# ladowarka.net
KiCad netlist of a schematic drawn in Altium Designer
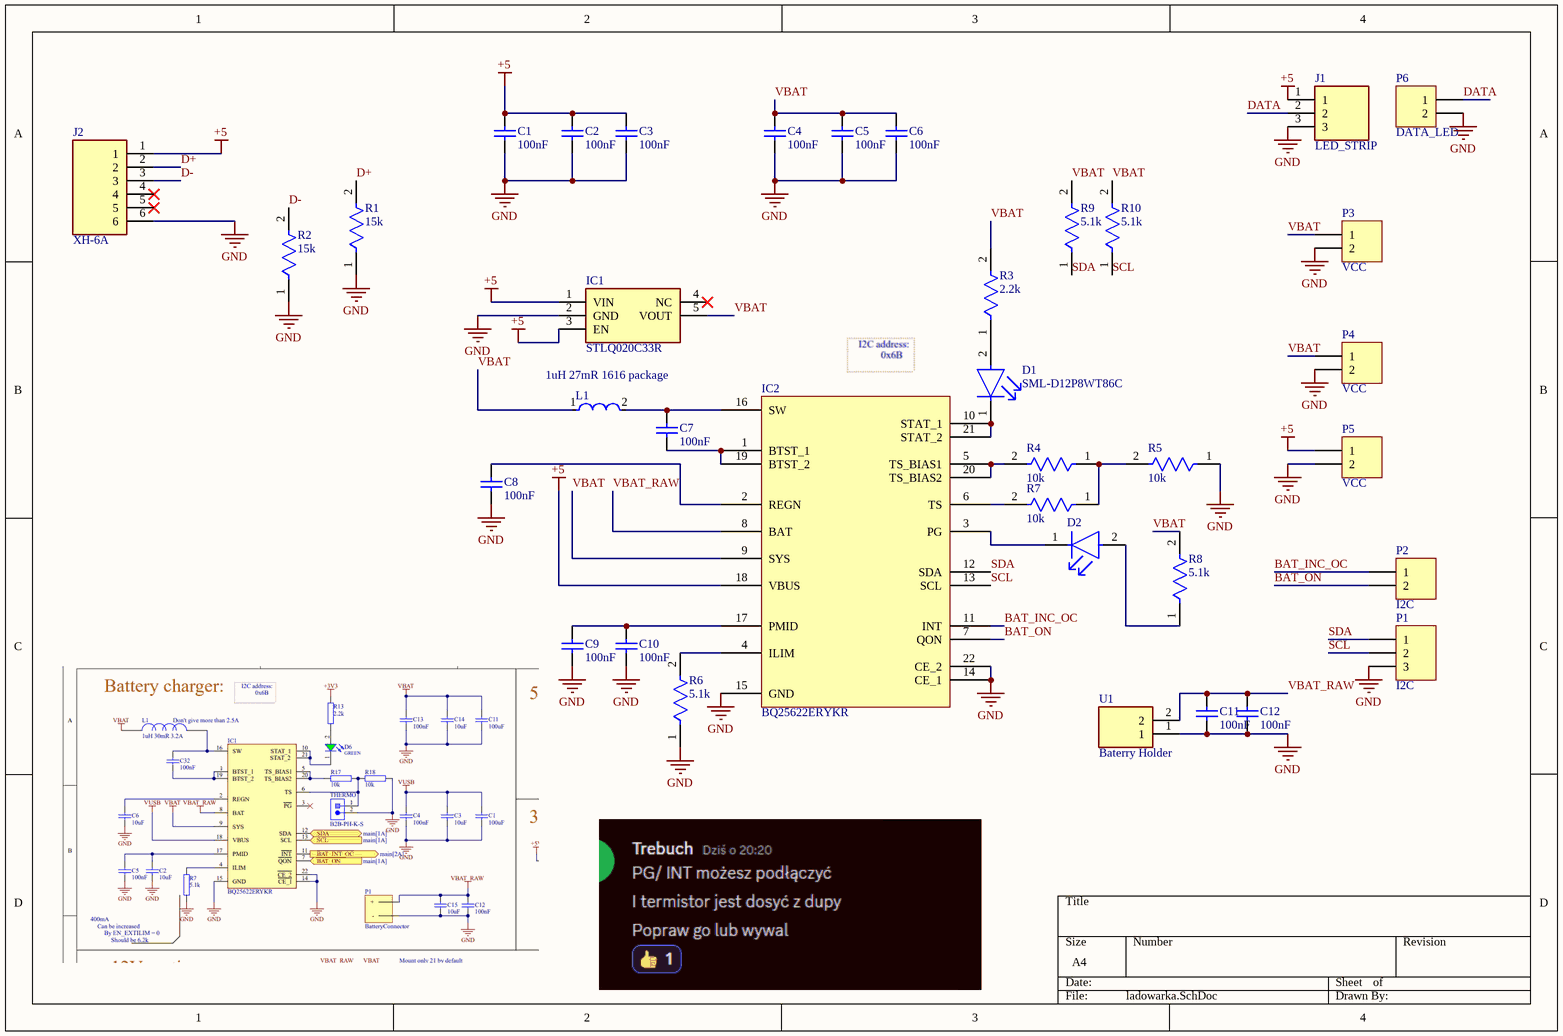
[diagram p0: ladowarka.SchDoc]

(export (version "E")
  (design (tool "Eeschema 10.0.6"))
  (components
    (comp (ref "C1")
      (value "100nF")
      (footprint "1608[0603]")
      (description "Capacitor (Semiconductor SIM Model)")
      (fields (field (name "PUBLISHER") "Altium Limited"))
      (libsource (lib "Miscellaneous Devices") (part "Cap Semi"))
    )
    (comp (ref "C2")
      (value "100nF")
      (footprint "1608[0603]")
      (description "Capacitor (Semiconductor SIM Model)")
      (fields (field (name "PUBLISHER") "Altium Limited"))
      (libsource (lib "Miscellaneous Devices") (part "Cap Semi"))
    )
    (comp (ref "C3")
      (value "100nF")
      (footprint "1608[0603]")
      (description "Capacitor (Semiconductor SIM Model)")
      (fields (field (name "PUBLISHER") "Altium Limited"))
      (libsource (lib "Miscellaneous Devices") (part "Cap Semi"))
    )
    (comp (ref "C4")
      (value "100nF")
      (footprint "1608[0603]")
      (description "Capacitor (Semiconductor SIM Model)")
      (fields (field (name "PUBLISHER") "Altium Limited"))
      (libsource (lib "Miscellaneous Devices") (part "Cap Semi"))
    )
    (comp (ref "C5")
      (value "100nF")
      (footprint "1608[0603]")
      (description "Capacitor (Semiconductor SIM Model)")
      (fields (field (name "PUBLISHER") "Altium Limited"))
      (libsource (lib "Miscellaneous Devices") (part "Cap Semi"))
    )
    (comp (ref "C6")
      (value "100nF")
      (footprint "1608[0603]")
      (description "Capacitor (Semiconductor SIM Model)")
      (fields (field (name "PUBLISHER") "Altium Limited"))
      (libsource (lib "Miscellaneous Devices") (part "Cap Semi"))
    )
    (comp (ref "C7")
      (value "100nF")
      (footprint "1608[0603]")
      (description "Capacitor (Semiconductor SIM Model)")
      (fields (field (name "PUBLISHER") "Altium Limited"))
      (libsource (lib "Miscellaneous Devices") (part "Cap Semi"))
    )
    (comp (ref "C8")
      (value "100nF")
      (footprint "1608[0603]")
      (description "Capacitor (Semiconductor SIM Model)")
      (fields (field (name "PUBLISHER") "Altium Limited"))
      (libsource (lib "Miscellaneous Devices") (part "Cap Semi"))
    )
    (comp (ref "C9")
      (value "100nF")
      (footprint "1608[0603]")
      (description "Capacitor (Semiconductor SIM Model)")
      (fields (field (name "PUBLISHER") "Altium Limited"))
      (libsource (lib "Miscellaneous Devices") (part "Cap Semi"))
    )
    (comp (ref "C10")
      (value "100nF")
      (footprint "1608[0603]")
      (description "Capacitor (Semiconductor SIM Model)")
      (fields (field (name "PUBLISHER") "Altium Limited"))
      (libsource (lib "Miscellaneous Devices") (part "Cap Semi"))
    )
    (comp (ref "C11")
      (value "100nF")
      (footprint "1608[0603]")
      (description "Capacitor (Semiconductor SIM Model)")
      (fields (field (name "PUBLISHER") "Altium Limited"))
      (libsource (lib "Miscellaneous Devices") (part "Cap Semi"))
    )
    (comp (ref "C12")
      (value "100nF")
      (footprint "1608[0603]")
      (description "Capacitor (Semiconductor SIM Model)")
      (fields (field (name "PUBLISHER") "Altium Limited"))
      (libsource (lib "Miscellaneous Devices") (part "Cap Semi"))
    )
    (comp (ref "D1")
      (value "SML-D12P8WT86C")
      (footprint "FP-SML-D12-MFG")
      (description "LED GREEN 1608 SMD")
      (fields
        (field (name "OCTOPART") "https://octopart.com/sml-d12p8wt86c-rohm-77740213")
        (field (name "MANUFACTURER") "Rohm")
      )
      (libsource (lib "Altium Content Vault") (part "8706943c75ba83719d021d2fdc84c58"))
    )
    (comp (ref "D2")
      (value "SML-D12P8WT86C")
      (footprint "FP-SML-D12-MFG")
      (description "LED GREEN 1608 SMD")
      (fields
        (field (name "OCTOPART") "https://octopart.com/sml-d12p8wt86c-rohm-77740213")
        (field (name "MANUFACTURER") "Rohm")
      )
      (libsource (lib "Altium Content Vault") (part "8706943c75ba83719d021d2fdc84c58"))
    )
    (comp (ref "IC1")
      (value "STLQ020C33R")
      (footprint "SamacSys:SOT65P210X110-5N")
      (description "Integrated Circuit")
      (fields (field (name "MOUSER PART NUMBER") "511-STLQ020C33R"))
      (libsource (lib "*") (part "STLQ020C33R"))
    )
    (comp (ref "IC2")
      (value "BQ25622ERYKR")
      (footprint "SamacSys:BQ25620RYKR")
      (description "Integrated Circuit")
      (fields
        (field (name "MANUFACTURER_PART_NUMBER") "BQ25620RYKR")
        (field (name "MOUSER PART NUMBER") "595-BQ25620RYKR")
      )
      (libsource (lib "SamacSys") (part "BQ25622ERYKR"))
    )
    (comp (ref "J1")
      (value "LED_STRIP")
      (footprint "SamacSys:SHDR3W64P0X250_1X3_990X575X700P")
      (description "Connector")
      (fields (field (name "MANUFACTURER_PART_NUMBER") "B3B-XH-A"))
      (libsource (lib "*") (part "B3B-XH-A"))
    )
    (comp (ref "J2")
      (value "XH-6A")
      (footprint "SamacSys:SHDR6W64P0X250_1X6_1750X580X720P")
      (description "Connector")
      (libsource (lib "*") (part "XH-6A"))
    )
    (comp (ref "L1")
      (value "1uH 27mR 1616 package")
      (footprint "FP-IHLP-1616BZ-FP_1_8545x-MFG")
      (description "Fixed Inductors Commercial Low DCR Series SMT 1uH 4.5A 27mΩ 20%")
      (fields (field (name "TOLERANCE") "20%"))
      (libsource (lib "Altium Content Vault") (part "725321dda6339637d4d059423bc1c3c"))
    )
    (comp (ref "P1")
      (value "I2C")
      (footprint "HDR1X3")
      (description "Header, 3-Pin")
      (fields (field (name "PUBLISHER") "Altium Limited"))
      (libsource (lib "Miscellaneous Connectors") (part "Header 3"))
    )
    (comp (ref "P2")
      (value "I2C")
      (footprint "HDR1X2")
      (description "Header, 2-Pin")
      (fields (field (name "PUBLISHER") "Altium Limited"))
      (libsource (lib "Miscellaneous Connectors") (part "Header 2"))
    )
    (comp (ref "P3")
      (value "VCC")
      (footprint "HDR1X2")
      (description "Header, 2-Pin")
      (fields (field (name "PUBLISHER") "Altium Limited"))
      (libsource (lib "Miscellaneous Connectors") (part "Header 2"))
    )
    (comp (ref "P4")
      (value "VCC")
      (footprint "HDR1X2")
      (description "Header, 2-Pin")
      (fields (field (name "PUBLISHER") "Altium Limited"))
      (libsource (lib "Miscellaneous Connectors") (part "Header 2"))
    )
    (comp (ref "P5")
      (value "VCC")
      (footprint "HDR1X2")
      (description "Header, 2-Pin")
      (fields (field (name "PUBLISHER") "Altium Limited"))
      (libsource (lib "Miscellaneous Connectors") (part "Header 2"))
    )
    (comp (ref "P6")
      (value "DATA_LED")
      (footprint "HDR1X2")
      (description "Header, 2-Pin")
      (fields (field (name "PUBLISHER") "Altium Limited"))
      (libsource (lib "") (part "Header 2_1"))
    )
    (comp (ref "R1")
      (value "15k")
      (footprint "FP-CRCW0603-e3-MFG")
      (description "RES Thick Film, 10kΩ, 1%, 0.1W, 100ppm/°C, 0603")
      (fields (field (name "TOLERANCE") "1%"))
      (libsource (lib "Altium Content Vault") (part "1029c3af85768c4190bb7ad29bc67b5"))
    )
    (comp (ref "R2")
      (value "15k")
      (footprint "FP-CRCW0603-e3-MFG")
      (description "RES Thick Film, 10kΩ, 1%, 0.1W, 100ppm/°C, 0603")
      (fields (field (name "TOLERANCE") "1%"))
      (libsource (lib "Altium Content Vault") (part "1029c3af85768c4190bb7ad29bc67b5"))
    )
    (comp (ref "R3")
      (value "2.2k")
      (footprint "FP-CRCW0603-e3-MFG")
      (description "RES Thick Film, 10kΩ, 1%, 0.1W, 100ppm/°C, 0603")
      (fields (field (name "TOLERANCE") "1%"))
      (libsource (lib "Altium Content Vault") (part "1029c3af85768c4190bb7ad29bc67b5"))
    )
    (comp (ref "R4")
      (value "10k")
      (footprint "FP-CRCW0603-e3-MFG")
      (description "RES Thick Film, 10kΩ, 1%, 0.1W, 100ppm/°C, 0603")
      (fields (field (name "TOLERANCE") "1%"))
      (libsource (lib "Altium Content Vault") (part "1029c3af85768c4190bb7ad29bc67b5"))
    )
    (comp (ref "R5")
      (value "10k")
      (footprint "FP-CRCW0603-e3-MFG")
      (description "RES Thick Film, 10kΩ, 1%, 0.1W, 100ppm/°C, 0603")
      (fields (field (name "TOLERANCE") "1%"))
      (libsource (lib "Altium Content Vault") (part "1029c3af85768c4190bb7ad29bc67b5"))
    )
    (comp (ref "R6")
      (value "5.1k")
      (footprint "FP-CRCW0603-e3-MFG")
      (description "RES Thick Film, 10kΩ, 1%, 0.1W, 100ppm/°C, 0603")
      (fields (field (name "TOLERANCE") "1%"))
      (libsource (lib "Altium Content Vault") (part "1029c3af85768c4190bb7ad29bc67b5"))
    )
    (comp (ref "R7")
      (value "10k")
      (footprint "FP-CRCW0603-e3-MFG")
      (description "RES Thick Film, 10kΩ, 1%, 0.1W, 100ppm/°C, 0603")
      (fields (field (name "TOLERANCE") "1%"))
      (libsource (lib "Altium Content Vault") (part "1029c3af85768c4190bb7ad29bc67b5"))
    )
    (comp (ref "R8")
      (value "5.1k")
      (footprint "FP-CRCW0603-e3-MFG")
      (description "RES Thick Film, 10kΩ, 1%, 0.1W, 100ppm/°C, 0603")
      (fields (field (name "TOLERANCE") "1%"))
      (libsource (lib "Altium Content Vault") (part "1029c3af85768c4190bb7ad29bc67b5"))
    )
    (comp (ref "R9")
      (value "5.1k")
      (footprint "FP-CRCW0603-e3-MFG")
      (description "RES Thick Film, 10kΩ, 1%, 0.1W, 100ppm/°C, 0603")
      (fields (field (name "TOLERANCE") "1%"))
      (libsource (lib "Altium Content Vault") (part "1029c3af85768c4190bb7ad29bc67b5"))
    )
    (comp (ref "R10")
      (value "5.1k")
      (footprint "FP-CRCW0603-e3-MFG")
      (description "RES Thick Film, 10kΩ, 1%, 0.1W, 100ppm/°C, 0603")
      (fields (field (name "TOLERANCE") "1%"))
      (libsource (lib "Altium Content Vault") (part "1029c3af85768c4190bb7ad29bc67b5"))
    )
    (comp (ref "U1")
      (value "Baterry Holder")
      (footprint "SamacSys:1053")
      (description "Undefined or Miscellaneous")
      (fields
        (field (name "MANUFACTURER_PART_NUMBER") "1053")
        (field (name "MOUSER PART NUMBER") "534-1053-BH")
      )
      (libsource (lib "SamacSys") (part "1053"))
    )
  )
  (nets
    (net (code "1") (name "+5") (class "Default")
      (node (ref "C1") (pin "1") (pinfunction "1_1") (pintype "passive"))
      (node (ref "C2") (pin "1") (pinfunction "1_1") (pintype "passive"))
      (node (ref "C3") (pin "1") (pinfunction "1_1") (pintype "passive"))
      (node (ref "IC1") (pin "1") (pinfunction "VIN_1") (pintype "passive"))
      (node (ref "IC1") (pin "3") (pinfunction "EN_3") (pintype "passive"))
      (node (ref "IC2") (pin "18") (pinfunction "VBUS_18") (pintype "passive"))
      (node (ref "J1") (pin "1") (pinfunction "1_1") (pintype "passive"))
      (node (ref "J2") (pin "1") (pinfunction "1_1") (pintype "passive"))
      (node (ref "P5") (pin "1") (pinfunction "1_1") (pintype "passive"))
    )
    (net (code "2") (name "/BAT_INC_OC") (class "Default")
      (node (ref "IC2") (pin "11") (pinfunction "INT_11") (pintype "passive"))
      (node (ref "P2") (pin "1") (pinfunction "1_1") (pintype "passive"))
    )
    (net (code "3") (name "/BAT_ON") (class "Default")
      (node (ref "IC2") (pin "7") (pinfunction "QON_7") (pintype "passive"))
      (node (ref "P2") (pin "2") (pinfunction "2_2") (pintype "passive"))
    )
    (net (code "4") (name "/D+") (class "Default")
      (node (ref "J2") (pin "2") (pinfunction "2_2") (pintype "passive"))
      (node (ref "R1") (pin "2") (pinfunction "2_2") (pintype "passive"))
    )
    (net (code "5") (name "/D-") (class "Default")
      (node (ref "J2") (pin "3") (pinfunction "3_3") (pintype "passive"))
      (node (ref "R2") (pin "2") (pinfunction "2_2") (pintype "passive"))
    )
    (net (code "6") (name "/DATA") (class "Default")
      (node (ref "J1") (pin "2") (pinfunction "2_2") (pintype "passive"))
      (node (ref "P6") (pin "1") (pinfunction "1_1") (pintype "passive"))
    )
    (net (code "7") (name "/SCL") (class "Default")
      (node (ref "IC2") (pin "13") (pinfunction "SCL_13") (pintype "passive"))
      (node (ref "P1") (pin "2") (pinfunction "2_2") (pintype "passive"))
      (node (ref "R10") (pin "1") (pinfunction "1_1") (pintype "passive"))
    )
    (net (code "8") (name "/SDA") (class "Default")
      (node (ref "IC2") (pin "12") (pinfunction "SDA_12") (pintype "passive"))
      (node (ref "P1") (pin "1") (pinfunction "1_1") (pintype "passive"))
      (node (ref "R9") (pin "1") (pinfunction "1_1") (pintype "passive"))
    )
    (net (code "9") (name "/VBAT") (class "Default")
      (node (ref "C4") (pin "1") (pinfunction "1_1") (pintype "passive"))
      (node (ref "C5") (pin "1") (pinfunction "1_1") (pintype "passive"))
      (node (ref "C6") (pin "1") (pinfunction "1_1") (pintype "passive"))
      (node (ref "IC1") (pin "5") (pinfunction "VOUT_5") (pintype "passive"))
      (node (ref "IC2") (pin "9") (pinfunction "SYS_9") (pintype "passive"))
      (node (ref "L1") (pin "1") (pinfunction "1_1") (pintype "passive"))
      (node (ref "P3") (pin "1") (pinfunction "1_1") (pintype "passive"))
      (node (ref "P4") (pin "1") (pinfunction "1_1") (pintype "passive"))
      (node (ref "R10") (pin "2") (pinfunction "2_2") (pintype "passive"))
      (node (ref "R3") (pin "2") (pinfunction "2_2") (pintype "passive"))
      (node (ref "R8") (pin "2") (pinfunction "2_2") (pintype "passive"))
      (node (ref "R9") (pin "2") (pinfunction "2_2") (pintype "passive"))
    )
    (net (code "10") (name "/VBAT_RAW") (class "Default")
      (node (ref "C11") (pin "1") (pinfunction "1_1") (pintype "passive"))
      (node (ref "C12") (pin "1") (pinfunction "1_1") (pintype "passive"))
      (node (ref "IC2") (pin "8") (pinfunction "BAT_8") (pintype "passive"))
      (node (ref "U1") (pin "2") (pinfunction "2_2") (pintype "passive"))
    )
    (net (code "11") (name "GND") (class "Default")
      (node (ref "C1") (pin "2") (pinfunction "2_2") (pintype "passive"))
      (node (ref "C10") (pin "2") (pinfunction "2_2") (pintype "passive"))
      (node (ref "C11") (pin "2") (pinfunction "2_2") (pintype "passive"))
      (node (ref "C12") (pin "2") (pinfunction "2_2") (pintype "passive"))
      (node (ref "C2") (pin "2") (pinfunction "2_2") (pintype "passive"))
      (node (ref "C3") (pin "2") (pinfunction "2_2") (pintype "passive"))
      (node (ref "C4") (pin "2") (pinfunction "2_2") (pintype "passive"))
      (node (ref "C5") (pin "2") (pinfunction "2_2") (pintype "passive"))
      (node (ref "C6") (pin "2") (pinfunction "2_2") (pintype "passive"))
      (node (ref "C8") (pin "2") (pinfunction "2_2") (pintype "passive"))
      (node (ref "C9") (pin "2") (pinfunction "2_2") (pintype "passive"))
      (node (ref "IC1") (pin "2") (pinfunction "GND_2") (pintype "passive"))
      (node (ref "IC2") (pin "14") (pinfunction "CE_1_14") (pintype "passive"))
      (node (ref "IC2") (pin "15") (pinfunction "GND_15") (pintype "passive"))
      (node (ref "IC2") (pin "22") (pinfunction "CE_2_22") (pintype "passive"))
      (node (ref "J1") (pin "3") (pinfunction "3_3") (pintype "passive"))
      (node (ref "J2") (pin "6") (pinfunction "6_6") (pintype "passive"))
      (node (ref "P1") (pin "3") (pinfunction "3_3") (pintype "passive"))
      (node (ref "P3") (pin "2") (pinfunction "2_2") (pintype "passive"))
      (node (ref "P4") (pin "2") (pinfunction "2_2") (pintype "passive"))
      (node (ref "P5") (pin "2") (pinfunction "2_2") (pintype "passive"))
      (node (ref "P6") (pin "2") (pinfunction "2_2") (pintype "passive"))
      (node (ref "R1") (pin "1") (pinfunction "1_1") (pintype "passive"))
      (node (ref "R2") (pin "1") (pinfunction "1_1") (pintype "passive"))
      (node (ref "R5") (pin "1") (pinfunction "1_1") (pintype "passive"))
      (node (ref "R6") (pin "1") (pinfunction "1_1") (pintype "passive"))
      (node (ref "U1") (pin "1") (pinfunction "1_1") (pintype "passive"))
    )
    (net (code "12") (name "Net-(D1-A)") (class "Default")
      (node (ref "D1") (pin "2") (pinfunction "A_2") (pintype "passive"))
      (node (ref "R3") (pin "1") (pinfunction "1_1") (pintype "passive"))
    )
    (net (code "13") (name "Net-(D1-C)") (class "Default")
      (node (ref "D1") (pin "1") (pinfunction "C_1") (pintype "passive"))
      (node (ref "IC2") (pin "10") (pinfunction "STAT_1_10") (pintype "passive"))
      (node (ref "IC2") (pin "21") (pinfunction "STAT_2_21") (pintype "passive"))
    )
    (net (code "14") (name "Net-(D2-A)") (class "Default")
      (node (ref "D2") (pin "2") (pinfunction "A_2") (pintype "passive"))
      (node (ref "R8") (pin "1") (pinfunction "1_1") (pintype "passive"))
    )
    (net (code "15") (name "Net-(D2-C)") (class "Default")
      (node (ref "D2") (pin "1") (pinfunction "C_1") (pintype "passive"))
      (node (ref "IC2") (pin "3") (pinfunction "PG_3") (pintype "passive"))
    )
    (net (code "16") (name "Net-(IC2-BTST_1)") (class "Default")
      (node (ref "C7") (pin "2") (pinfunction "2_2") (pintype "passive"))
      (node (ref "IC2") (pin "1") (pinfunction "BTST_1_1") (pintype "passive"))
      (node (ref "IC2") (pin "19") (pinfunction "BTST_2_19") (pintype "passive"))
    )
    (net (code "17") (name "Net-(IC2-ILIM)") (class "Default")
      (node (ref "IC2") (pin "4") (pinfunction "ILIM_4") (pintype "passive"))
      (node (ref "R6") (pin "2") (pinfunction "2_2") (pintype "passive"))
    )
    (net (code "18") (name "Net-(IC2-PMID)") (class "Default")
      (node (ref "C10") (pin "1") (pinfunction "1_1") (pintype "passive"))
      (node (ref "C9") (pin "1") (pinfunction "1_1") (pintype "passive"))
      (node (ref "IC2") (pin "17") (pinfunction "PMID_17") (pintype "passive"))
    )
    (net (code "19") (name "Net-(IC2-REGN)") (class "Default")
      (node (ref "C8") (pin "1") (pinfunction "1_1") (pintype "passive"))
      (node (ref "IC2") (pin "2") (pinfunction "REGN_2") (pintype "passive"))
    )
    (net (code "20") (name "Net-(IC2-SW)") (class "Default")
      (node (ref "C7") (pin "1") (pinfunction "1_1") (pintype "passive"))
      (node (ref "IC2") (pin "16") (pinfunction "SW_16") (pintype "passive"))
      (node (ref "L1") (pin "2") (pinfunction "2_2") (pintype "passive"))
    )
    (net (code "21") (name "Net-(IC2-TS)") (class "Default")
      (node (ref "IC2") (pin "6") (pinfunction "TS_6") (pintype "passive"))
      (node (ref "R7") (pin "2") (pinfunction "2_2") (pintype "passive"))
    )
    (net (code "22") (name "Net-(IC2-TS_BIAS1)") (class "Default")
      (node (ref "IC2") (pin "20") (pinfunction "TS_BIAS2_20") (pintype "passive"))
      (node (ref "IC2") (pin "5") (pinfunction "TS_BIAS1_5") (pintype "passive"))
      (node (ref "R4") (pin "2") (pinfunction "2_2") (pintype "passive"))
    )
    (net (code "23") (name "Net-(R4-Pad1)") (class "Default")
      (node (ref "R4") (pin "1") (pinfunction "1_1") (pintype "passive"))
      (node (ref "R5") (pin "2") (pinfunction "2_2") (pintype "passive"))
      (node (ref "R7") (pin "1") (pinfunction "1_1") (pintype "passive"))
    )
    (net (code "24") (name "unconnected-(IC1-NC-Pad4)") (class "Default")
      (node (ref "IC1") (pin "4") (pinfunction "NC_4") (pintype "passive+no_connect"))
    )
    (net (code "25") (name "unconnected-(J2-Pad4)") (class "Default")
      (node (ref "J2") (pin "4") (pinfunction "4_4") (pintype "passive+no_connect"))
    )
    (net (code "26") (name "unconnected-(J2-Pad5)") (class "Default")
      (node (ref "J2") (pin "5") (pinfunction "5_5") (pintype "passive+no_connect"))
    )
  )
)
